# mixer-preamp.net
KiCad netlist of a schematic drawn in EAGLE
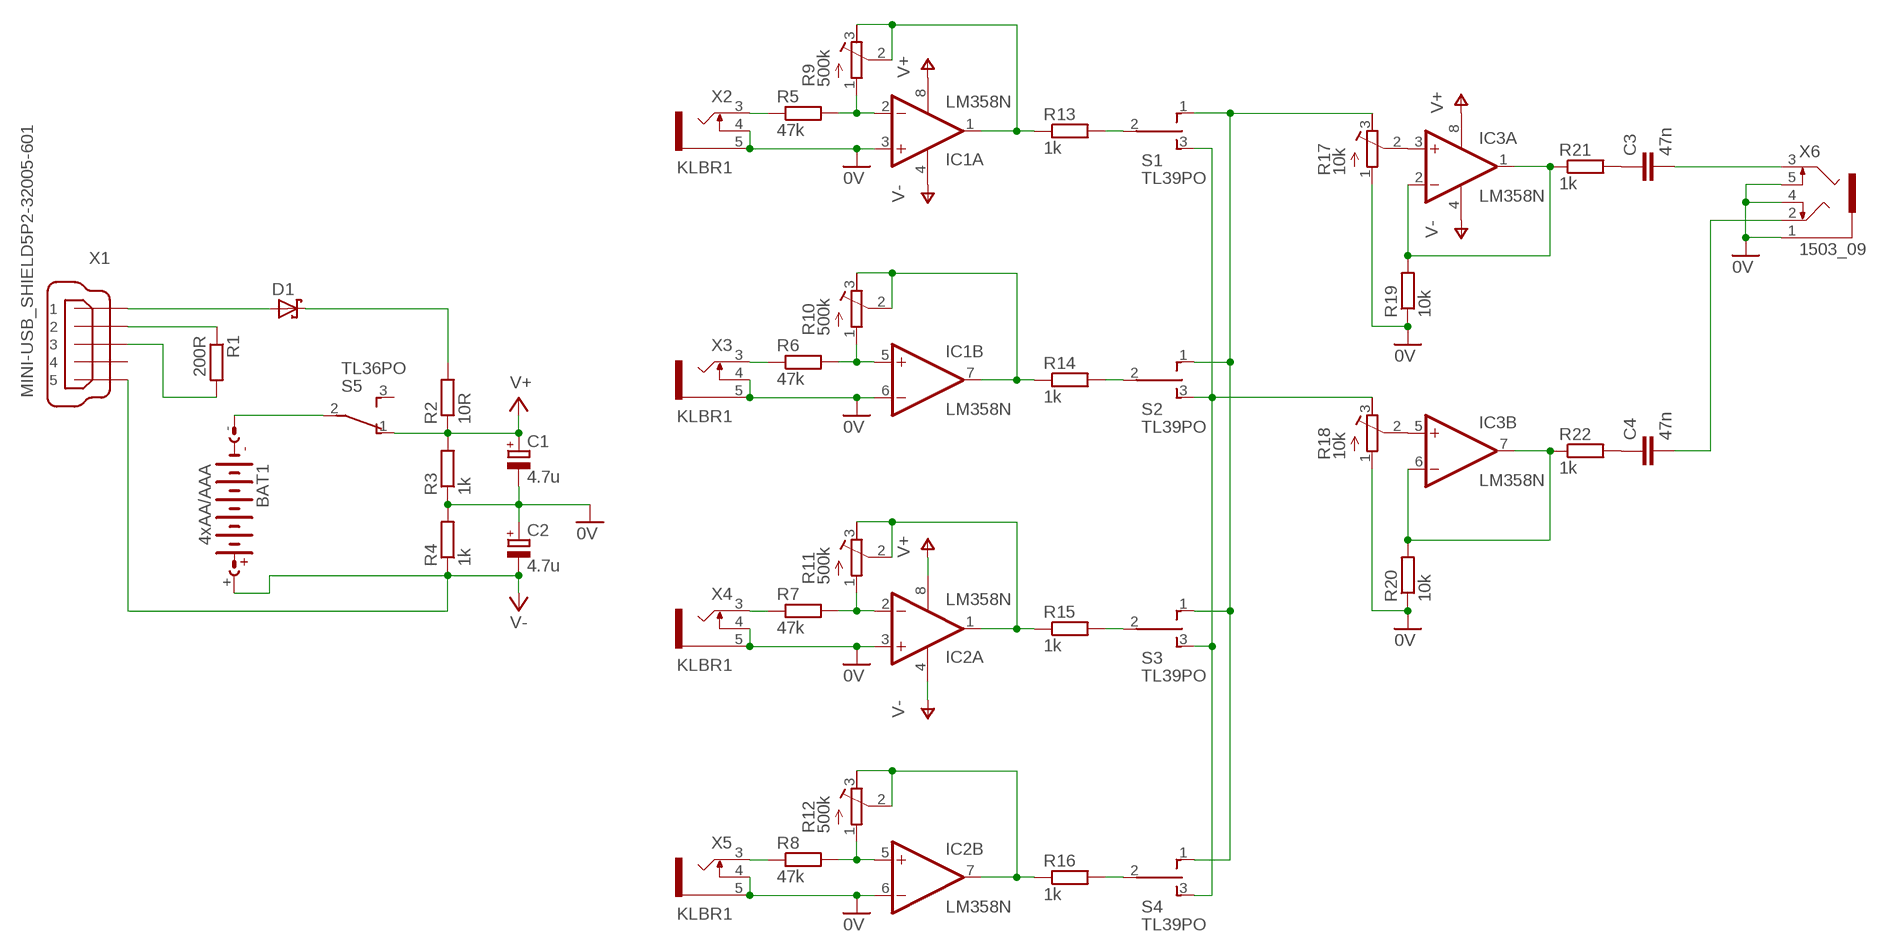
[diagram p0: schematic, sheet 1]

(export (version "E")
  (design (tool "Eeschema 10.0.6"))
  (components
    (comp (ref "BAT1")
      (value "4xAA/AAA")
      (footprint "eagle-import:AB9V")
      (libsource (lib "eagle-import") (part "AB9V"))
    )
    (comp (ref "C1")
      (value "4.7u")
      (footprint "eagle-import:E5-5")
      (libsource (lib "eagle-import") (part "CPOL-EUE5-5"))
    )
    (comp (ref "C2")
      (value "4.7u")
      (footprint "eagle-import:E5-5")
      (libsource (lib "eagle-import") (part "CPOL-EUE5-5"))
    )
    (comp (ref "C3")
      (value "47n")
      (footprint "eagle-import:C025-024X044")
      (libsource (lib "eagle-import") (part "C-EU025-024X044"))
    )
    (comp (ref "C4")
      (value "47n")
      (footprint "eagle-import:C025-024X044")
      (libsource (lib "eagle-import") (part "C-EU025-024X044"))
    )
    (comp (ref "D1")
      (value "SCHOTTKY-DIODEDO35-7")
      (footprint "eagle-import:DO35-7")
      (libsource (lib "eagle-import") (part "SCHOTTKY-DIODEDO35-7"))
    )
    (comp (ref "IC1")
      (value "LM358N")
      (footprint "eagle-import:DIL08")
      (libsource (lib "eagle-import") (part "LM358N"))
    )
    (comp (ref "IC2")
      (value "LM358N")
      (footprint "eagle-import:DIL08")
      (libsource (lib "eagle-import") (part "LM358N"))
    )
    (comp (ref "IC3")
      (value "LM358N")
      (footprint "eagle-import:DIL08")
      (libsource (lib "eagle-import") (part "LM358N"))
    )
    (comp (ref "R1")
      (value "200R")
      (footprint "eagle-import:0204V")
      (libsource (lib "eagle-import") (part "R-EU_0204/2V"))
    )
    (comp (ref "R2")
      (value "10R")
      (footprint "eagle-import:0204_7")
      (libsource (lib "eagle-import") (part "R-EU_0204/7"))
    )
    (comp (ref "R3")
      (value "1k")
      (footprint "eagle-import:0204V")
      (libsource (lib "eagle-import") (part "R-EU_0204/2V"))
    )
    (comp (ref "R4")
      (value "1k")
      (footprint "eagle-import:0204V")
      (libsource (lib "eagle-import") (part "R-EU_0204/2V"))
    )
    (comp (ref "R5")
      (value "47k")
      (footprint "eagle-import:0207_10")
      (libsource (lib "eagle-import") (part "R-EU_0207/10"))
    )
    (comp (ref "R6")
      (value "47k")
      (footprint "eagle-import:0207_10")
      (libsource (lib "eagle-import") (part "R-EU_0207/10"))
    )
    (comp (ref "R7")
      (value "47k")
      (footprint "eagle-import:0207_10")
      (libsource (lib "eagle-import") (part "R-EU_0207/10"))
    )
    (comp (ref "R8")
      (value "47k")
      (footprint "eagle-import:0207_10")
      (libsource (lib "eagle-import") (part "R-EU_0207/10"))
    )
    (comp (ref "R9")
      (value "500k")
      (footprint "eagle-import:RTRIM3296W")
      (libsource (lib "eagle-import") (part "R-TRIMM3296W"))
    )
    (comp (ref "R10")
      (value "500k")
      (footprint "eagle-import:RTRIM3296W")
      (libsource (lib "eagle-import") (part "R-TRIMM3296W"))
    )
    (comp (ref "R11")
      (value "500k")
      (footprint "eagle-import:RTRIM3296W")
      (libsource (lib "eagle-import") (part "R-TRIMM3296W"))
    )
    (comp (ref "R12")
      (value "500k")
      (footprint "eagle-import:RTRIM3296W")
      (libsource (lib "eagle-import") (part "R-TRIMM3296W"))
    )
    (comp (ref "R13")
      (value "1k")
      (footprint "eagle-import:0207_10")
      (libsource (lib "eagle-import") (part "R-EU_0207/10"))
    )
    (comp (ref "R14")
      (value "1k")
      (footprint "eagle-import:0207_10")
      (libsource (lib "eagle-import") (part "R-EU_0207/10"))
    )
    (comp (ref "R15")
      (value "1k")
      (footprint "eagle-import:0207_10")
      (libsource (lib "eagle-import") (part "R-EU_0207/10"))
    )
    (comp (ref "R16")
      (value "1k")
      (footprint "eagle-import:0207_10")
      (libsource (lib "eagle-import") (part "R-EU_0207/10"))
    )
    (comp (ref "R17")
      (value "10k")
      (footprint "eagle-import:RTRIM3296W")
      (libsource (lib "eagle-import") (part "R-TRIMM3296W"))
    )
    (comp (ref "R18")
      (value "10k")
      (footprint "eagle-import:RTRIM3296W")
      (libsource (lib "eagle-import") (part "R-TRIMM3296W"))
    )
    (comp (ref "R19")
      (value "10k")
      (footprint "eagle-import:0207_10")
      (libsource (lib "eagle-import") (part "R-EU_0207/10"))
    )
    (comp (ref "R20")
      (value "10k")
      (footprint "eagle-import:0207_10")
      (libsource (lib "eagle-import") (part "R-EU_0207/10"))
    )
    (comp (ref "R21")
      (value "1k")
      (footprint "eagle-import:0207_10")
      (libsource (lib "eagle-import") (part "R-EU_0207/10"))
    )
    (comp (ref "R22")
      (value "1k")
      (footprint "eagle-import:0207_10")
      (libsource (lib "eagle-import") (part "R-EU_0207/10"))
    )
    (comp (ref "S1")
      (value "TL39PO")
      (footprint "eagle-import:TL3XPO")
      (libsource (lib "eagle-import") (part "TL39PO"))
    )
    (comp (ref "S2")
      (value "TL39PO")
      (footprint "eagle-import:TL3XPO")
      (libsource (lib "eagle-import") (part "TL39PO"))
    )
    (comp (ref "S3")
      (value "TL39PO")
      (footprint "eagle-import:TL3XPO")
      (libsource (lib "eagle-import") (part "TL39PO"))
    )
    (comp (ref "S4")
      (value "TL39PO")
      (footprint "eagle-import:TL3XPO")
      (libsource (lib "eagle-import") (part "TL39PO"))
    )
    (comp (ref "S5")
      (value "TL36PO")
      (footprint "eagle-import:TL3XPO")
      (libsource (lib "eagle-import") (part "TL36PO"))
    )
    (comp (ref "X1")
      (value "MINI-USB_SHIELD5P2-32005-601")
      (footprint "eagle-import:32005-601")
      (libsource (lib "eagle-import") (part "MINI-USB_SHIELD5P2-32005-601"))
    )
    (comp (ref "X2")
      (value "KLBR1")
      (footprint "eagle-import:KLBR1")
      (fields (field (name "MPN") "KLBR 1"))
      (libsource (lib "eagle-import") (part "KLBR?1"))
    )
    (comp (ref "X3")
      (value "KLBR1")
      (footprint "eagle-import:KLBR1")
      (fields (field (name "MPN") "KLBR 1"))
      (libsource (lib "eagle-import") (part "KLBR?1"))
    )
    (comp (ref "X4")
      (value "KLBR1")
      (footprint "eagle-import:KLBR1")
      (fields (field (name "MPN") "KLBR 1"))
      (libsource (lib "eagle-import") (part "KLBR?1"))
    )
    (comp (ref "X5")
      (value "KLBR1")
      (footprint "eagle-import:KLBR1")
      (fields (field (name "MPN") "KLBR 1"))
      (libsource (lib "eagle-import") (part "KLBR?1"))
    )
    (comp (ref "X6")
      (value "1503_09")
      (footprint "eagle-import:1503_09")
      (libsource (lib "eagle-import") (part "1503_09"))
    )
  )
  (nets
    (net (code "1") (name "0V") (class "Default")
      (node (ref "C1") (pin "-") (pinfunction "-_-") (pintype "passive"))
      (node (ref "C2") (pin "+") (pinfunction "+_+") (pintype "passive"))
      (node (ref "IC1") (pin "3") (pinfunction "+IN_3") (pintype "input"))
      (node (ref "IC1") (pin "6") (pinfunction "-IN_6") (pintype "input"))
      (node (ref "IC2") (pin "3") (pinfunction "+IN_3") (pintype "input"))
      (node (ref "IC2") (pin "6") (pinfunction "-IN_6") (pintype "input"))
      (node (ref "R17") (pin "1") (pinfunction "A_1") (pintype "passive"))
      (node (ref "R18") (pin "1") (pinfunction "A_1") (pintype "passive"))
      (node (ref "R19") (pin "1") (pinfunction "1_1") (pintype "passive"))
      (node (ref "R20") (pin "1") (pinfunction "1_1") (pintype "passive"))
      (node (ref "R3") (pin "1") (pinfunction "1_1") (pintype "passive"))
      (node (ref "R4") (pin "2") (pinfunction "2_2") (pintype "passive"))
      (node (ref "X2") (pin "4") (pinfunction "4_4") (pintype "passive"))
      (node (ref "X2") (pin "5") (pinfunction "5_5") (pintype "passive"))
      (node (ref "X3") (pin "4") (pinfunction "4_4") (pintype "passive"))
      (node (ref "X3") (pin "5") (pinfunction "5_5") (pintype "passive"))
      (node (ref "X4") (pin "4") (pinfunction "4_4") (pintype "passive"))
      (node (ref "X4") (pin "5") (pinfunction "5_5") (pintype "passive"))
      (node (ref "X5") (pin "4") (pinfunction "4_4") (pintype "passive"))
      (node (ref "X5") (pin "5") (pinfunction "5_5") (pintype "passive"))
      (node (ref "X6") (pin "1") (pinfunction "1_1") (pintype "passive"))
      (node (ref "X6") (pin "4") (pinfunction "4_4") (pintype "passive"))
      (node (ref "X6") (pin "5") (pinfunction "5_5") (pintype "passive"))
    )
    (net (code "2") (name "Net-(C3-Pad1)") (class "Default")
      (node (ref "C3") (pin "1") (pinfunction "1_1") (pintype "passive"))
      (node (ref "R21") (pin "2") (pinfunction "2_2") (pintype "passive"))
    )
    (net (code "3") (name "Net-(C3-Pad2)") (class "Default")
      (node (ref "C3") (pin "2") (pinfunction "2_2") (pintype "passive"))
      (node (ref "X6") (pin "3") (pinfunction "3_3") (pintype "passive"))
    )
    (net (code "4") (name "Net-(C4-Pad1)") (class "Default")
      (node (ref "C4") (pin "1") (pinfunction "1_1") (pintype "passive"))
      (node (ref "R22") (pin "2") (pinfunction "2_2") (pintype "passive"))
    )
    (net (code "5") (name "Net-(C4-Pad2)") (class "Default")
      (node (ref "C4") (pin "2") (pinfunction "2_2") (pintype "passive"))
      (node (ref "X6") (pin "2") (pinfunction "2_2") (pintype "passive"))
    )
    (net (code "6") (name "Net-(D1-PadA)") (class "Default")
      (node (ref "D1") (pin "A") (pinfunction "A_A") (pintype "passive"))
      (node (ref "X1") (pin "1") (pinfunction "1_1") (pintype "passive"))
    )
    (net (code "7") (name "Net-(D1-PadC)") (class "Default")
      (node (ref "D1") (pin "C") (pinfunction "C_C") (pintype "passive"))
      (node (ref "R2") (pin "2") (pinfunction "2_2") (pintype "passive"))
    )
    (net (code "8") (name "Net-(IC1A--IN)") (class "Default")
      (node (ref "IC1") (pin "2") (pinfunction "-IN_2") (pintype "input"))
      (node (ref "R5") (pin "2") (pinfunction "2_2") (pintype "passive"))
      (node (ref "R9") (pin "1") (pinfunction "A_1") (pintype "passive"))
    )
    (net (code "9") (name "Net-(IC1A-OUT)") (class "Default")
      (node (ref "IC1") (pin "1") (pinfunction "OUT_1") (pintype "output"))
      (node (ref "R13") (pin "1") (pinfunction "1_1") (pintype "passive"))
      (node (ref "R9") (pin "2") (pinfunction "S_2") (pintype "passive"))
      (node (ref "R9") (pin "3") (pinfunction "E_3") (pintype "passive"))
    )
    (net (code "10") (name "Net-(IC1B-+IN)") (class "Default")
      (node (ref "IC1") (pin "5") (pinfunction "+IN_5") (pintype "input"))
      (node (ref "R10") (pin "1") (pinfunction "A_1") (pintype "passive"))
      (node (ref "R6") (pin "2") (pinfunction "2_2") (pintype "passive"))
    )
    (net (code "11") (name "Net-(IC1B-OUT)") (class "Default")
      (node (ref "IC1") (pin "7") (pinfunction "OUT_7") (pintype "output"))
      (node (ref "R10") (pin "2") (pinfunction "S_2") (pintype "passive"))
      (node (ref "R10") (pin "3") (pinfunction "E_3") (pintype "passive"))
      (node (ref "R14") (pin "1") (pinfunction "1_1") (pintype "passive"))
    )
    (net (code "12") (name "Net-(IC2A--IN)") (class "Default")
      (node (ref "IC2") (pin "2") (pinfunction "-IN_2") (pintype "input"))
      (node (ref "R11") (pin "1") (pinfunction "A_1") (pintype "passive"))
      (node (ref "R7") (pin "2") (pinfunction "2_2") (pintype "passive"))
    )
    (net (code "13") (name "Net-(IC2A-OUT)") (class "Default")
      (node (ref "IC2") (pin "1") (pinfunction "OUT_1") (pintype "output"))
      (node (ref "R11") (pin "2") (pinfunction "S_2") (pintype "passive"))
      (node (ref "R11") (pin "3") (pinfunction "E_3") (pintype "passive"))
      (node (ref "R15") (pin "1") (pinfunction "1_1") (pintype "passive"))
    )
    (net (code "14") (name "Net-(IC2B-+IN)") (class "Default")
      (node (ref "IC2") (pin "5") (pinfunction "+IN_5") (pintype "input"))
      (node (ref "R12") (pin "1") (pinfunction "A_1") (pintype "passive"))
      (node (ref "R8") (pin "2") (pinfunction "2_2") (pintype "passive"))
    )
    (net (code "15") (name "Net-(IC2B-OUT)") (class "Default")
      (node (ref "IC2") (pin "7") (pinfunction "OUT_7") (pintype "output"))
      (node (ref "R12") (pin "2") (pinfunction "S_2") (pintype "passive"))
      (node (ref "R12") (pin "3") (pinfunction "E_3") (pintype "passive"))
      (node (ref "R16") (pin "1") (pinfunction "1_1") (pintype "passive"))
    )
    (net (code "16") (name "Net-(IC3A-+IN)") (class "Default")
      (node (ref "IC3") (pin "3") (pinfunction "+IN_3") (pintype "input"))
      (node (ref "R17") (pin "2") (pinfunction "S_2") (pintype "passive"))
    )
    (net (code "17") (name "Net-(IC3A--IN)") (class "Default")
      (node (ref "IC3") (pin "1") (pinfunction "OUT_1") (pintype "output"))
      (node (ref "IC3") (pin "2") (pinfunction "-IN_2") (pintype "input"))
      (node (ref "R19") (pin "2") (pinfunction "2_2") (pintype "passive"))
      (node (ref "R21") (pin "1") (pinfunction "1_1") (pintype "passive"))
    )
    (net (code "18") (name "Net-(IC3B-+IN)") (class "Default")
      (node (ref "IC3") (pin "5") (pinfunction "+IN_5") (pintype "input"))
      (node (ref "R18") (pin "2") (pinfunction "S_2") (pintype "passive"))
    )
    (net (code "19") (name "Net-(IC3B--IN)") (class "Default")
      (node (ref "IC3") (pin "6") (pinfunction "-IN_6") (pintype "input"))
      (node (ref "IC3") (pin "7") (pinfunction "OUT_7") (pintype "output"))
      (node (ref "R20") (pin "2") (pinfunction "2_2") (pintype "passive"))
      (node (ref "R22") (pin "1") (pinfunction "1_1") (pintype "passive"))
    )
    (net (code "20") (name "Net-(R1-Pad1)") (class "Default")
      (node (ref "R1") (pin "1") (pinfunction "1_1") (pintype "passive"))
      (node (ref "X1") (pin "2") (pinfunction "2_2") (pintype "passive"))
    )
    (net (code "21") (name "Net-(R1-Pad2)") (class "Default")
      (node (ref "R1") (pin "2") (pinfunction "2_2") (pintype "passive"))
      (node (ref "X1") (pin "3") (pinfunction "3_3") (pintype "passive"))
    )
    (net (code "22") (name "Net-(R5-Pad1)") (class "Default")
      (node (ref "R5") (pin "1") (pinfunction "1_1") (pintype "passive"))
      (node (ref "X2") (pin "3") (pinfunction "3_3") (pintype "passive"))
    )
    (net (code "23") (name "Net-(R6-Pad1)") (class "Default")
      (node (ref "R6") (pin "1") (pinfunction "1_1") (pintype "passive"))
      (node (ref "X3") (pin "3") (pinfunction "3_3") (pintype "passive"))
    )
    (net (code "24") (name "Net-(R7-Pad1)") (class "Default")
      (node (ref "R7") (pin "1") (pinfunction "1_1") (pintype "passive"))
      (node (ref "X4") (pin "3") (pinfunction "3_3") (pintype "passive"))
    )
    (net (code "25") (name "Net-(R8-Pad1)") (class "Default")
      (node (ref "R8") (pin "1") (pinfunction "1_1") (pintype "passive"))
      (node (ref "X5") (pin "3") (pinfunction "3_3") (pintype "passive"))
    )
    (net (code "26") (name "Net-(R17-E)") (class "Default")
      (node (ref "R17") (pin "3") (pinfunction "E_3") (pintype "passive"))
      (node (ref "S1") (pin "1") (pinfunction "O_1") (pintype "passive"))
      (node (ref "S2") (pin "1") (pinfunction "O_1") (pintype "passive"))
      (node (ref "S3") (pin "1") (pinfunction "O_1") (pintype "passive"))
      (node (ref "S4") (pin "1") (pinfunction "O_1") (pintype "passive"))
    )
    (net (code "27") (name "Net-(R18-E)") (class "Default")
      (node (ref "R18") (pin "3") (pinfunction "E_3") (pintype "passive"))
      (node (ref "S1") (pin "3") (pinfunction "S_3") (pintype "passive"))
      (node (ref "S2") (pin "3") (pinfunction "S_3") (pintype "passive"))
      (node (ref "S3") (pin "3") (pinfunction "S_3") (pintype "passive"))
      (node (ref "S4") (pin "3") (pinfunction "S_3") (pintype "passive"))
    )
    (net (code "28") (name "Net-(S1-P)") (class "Default")
      (node (ref "R13") (pin "2") (pinfunction "2_2") (pintype "passive"))
      (node (ref "S1") (pin "2") (pinfunction "P_2") (pintype "passive"))
    )
    (net (code "29") (name "Net-(S2-P)") (class "Default")
      (node (ref "R14") (pin "2") (pinfunction "2_2") (pintype "passive"))
      (node (ref "S2") (pin "2") (pinfunction "P_2") (pintype "passive"))
    )
    (net (code "30") (name "Net-(S3-P)") (class "Default")
      (node (ref "R15") (pin "2") (pinfunction "2_2") (pintype "passive"))
      (node (ref "S3") (pin "2") (pinfunction "P_2") (pintype "passive"))
    )
    (net (code "31") (name "Net-(S4-P)") (class "Default")
      (node (ref "R16") (pin "2") (pinfunction "2_2") (pintype "passive"))
      (node (ref "S4") (pin "2") (pinfunction "P_2") (pintype "passive"))
    )
    (net (code "32") (name "Net-(S5-P)") (class "Default")
      (node (ref "BAT1") (pin "-") (pinfunction "-_-") (pintype "passive"))
      (node (ref "S5") (pin "2") (pinfunction "P_2") (pintype "passive"))
    )
    (net (code "33") (name "V+") (class "Default")
      (node (ref "C1") (pin "+") (pinfunction "+_+") (pintype "passive"))
      (node (ref "IC1") (pin "8") (pinfunction "V+_8") (pintype "power_in"))
      (node (ref "IC2") (pin "8") (pinfunction "V+_8") (pintype "power_in"))
      (node (ref "IC3") (pin "8") (pinfunction "V+_8") (pintype "power_in"))
      (node (ref "R2") (pin "1") (pinfunction "1_1") (pintype "passive"))
      (node (ref "R3") (pin "2") (pinfunction "2_2") (pintype "passive"))
      (node (ref "S5") (pin "1") (pinfunction "O_1") (pintype "passive"))
    )
    (net (code "34") (name "V-") (class "Default")
      (node (ref "BAT1") (pin "+") (pinfunction "+_+") (pintype "passive"))
      (node (ref "C2") (pin "-") (pinfunction "-_-") (pintype "passive"))
      (node (ref "IC1") (pin "4") (pinfunction "V-_4") (pintype "power_in"))
      (node (ref "IC2") (pin "4") (pinfunction "V-_4") (pintype "power_in"))
      (node (ref "IC3") (pin "4") (pinfunction "V-_4") (pintype "power_in"))
      (node (ref "R4") (pin "1") (pinfunction "1_1") (pintype "passive"))
      (node (ref "X1") (pin "5") (pinfunction "5_5") (pintype "passive"))
    )
    (net (code "35") (name "unconnected-(S5-S-Pad3)") (class "Default")
      (node (ref "S5") (pin "3") (pinfunction "S_3") (pintype "passive"))
    )
    (net (code "36") (name "unconnected-(X1-Pad4)") (class "Default")
      (node (ref "X1") (pin "4") (pinfunction "4_4") (pintype "passive"))
    )
  )
)
